# QTR.net
KiCad netlist of a schematic drawn in Altium Designer
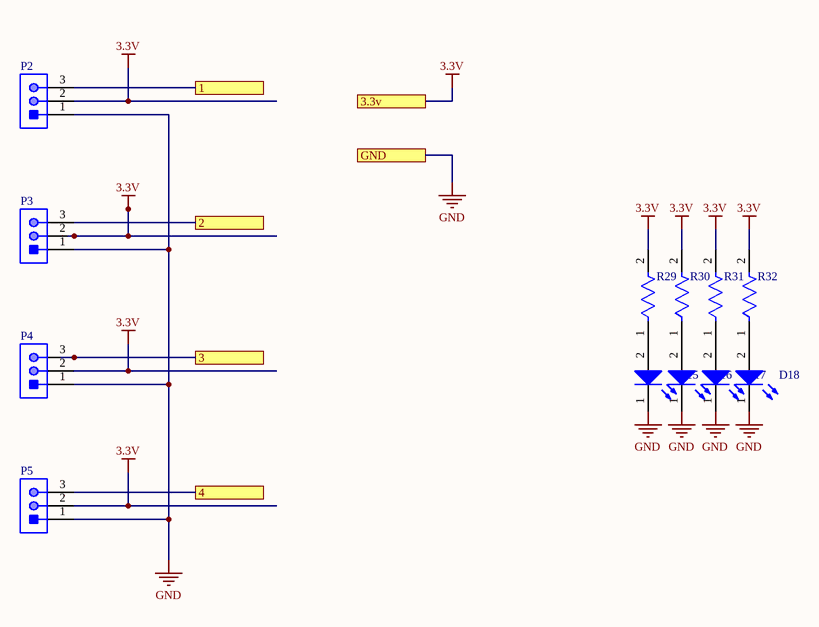
[diagram p0: QTR.SchDoc]

(export (version "E")
  (design (tool "Eeschema 10.0.6"))
  (components
    (comp (ref "D15")
      (value "150080BS75000")
      (footprint "WL-SMCW_0805_150080xx75000")
      (libsource (lib "Altium Content Vault") (part "LED_Blue_2A-1K"))
    )
    (comp (ref "D16")
      (value "150080BS75000")
      (footprint "WL-SMCW_0805_150080xx75000")
      (libsource (lib "Altium Content Vault") (part "LED_Blue_2A-1K"))
    )
    (comp (ref "D17")
      (value "150080BS75000")
      (footprint "WL-SMCW_0805_150080xx75000")
      (libsource (lib "Altium Content Vault") (part "LED_Blue_2A-1K"))
    )
    (comp (ref "D18")
      (value "150080BS75000")
      (footprint "WL-SMCW_0805_150080xx75000")
      (libsource (lib "Altium Content Vault") (part "LED_Blue_2A-1K"))
    )
    (comp (ref "P2")
      (value "B3B-PH-K-S(LF)(SN)")
      (footprint "JST-B3B-PH-K-S-3_V")
      (fields (field (name "MANUFACTURER") "JST"))
      (libsource (lib "Altium Content Vault") (part "CN-1P-M-R3"))
    )
    (comp (ref "P3")
      (value "B3B-PH-K-S(LF)(SN)")
      (footprint "JST-B3B-PH-K-S-3_V")
      (fields (field (name "MANUFACTURER") "JST"))
      (libsource (lib "Altium Content Vault") (part "CN-1P-M-R3"))
    )
    (comp (ref "P4")
      (value "B3B-PH-K-S(LF)(SN)")
      (footprint "JST-B3B-PH-K-S-3_V")
      (fields (field (name "MANUFACTURER") "JST"))
      (libsource (lib "Altium Content Vault") (part "CN-1P-M-R3"))
    )
    (comp (ref "P5")
      (value "B3B-PH-K-S(LF)(SN)")
      (footprint "JST-B3B-PH-K-S-3_V")
      (fields (field (name "MANUFACTURER") "JST"))
      (libsource (lib "Altium Content Vault") (part "CN-1P-M-R3"))
    )
    (comp (ref "R29")
      (value "ERJ-6ENF1500V")
      (footprint "FP-ERJ6EN-IPC_A")
      (fields (field (name "TOLERANCE") "1%"))
      (libsource (lib "Altium Content Vault") (part "1029c3af85768c4190bb7ad29bc67b5"))
    )
    (comp (ref "R30")
      (value "ERJ-6ENF1500V")
      (footprint "FP-ERJ6EN-IPC_A")
      (fields (field (name "TOLERANCE") "1%"))
      (libsource (lib "Altium Content Vault") (part "1029c3af85768c4190bb7ad29bc67b5"))
    )
    (comp (ref "R31")
      (value "ERJ-6ENF1500V")
      (footprint "FP-ERJ6EN-IPC_A")
      (fields (field (name "TOLERANCE") "1%"))
      (libsource (lib "Altium Content Vault") (part "1029c3af85768c4190bb7ad29bc67b5"))
    )
    (comp (ref "R32")
      (value "ERJ-6ENF1500V")
      (footprint "FP-ERJ6EN-IPC_A")
      (fields (field (name "TOLERANCE") "1%"))
      (libsource (lib "Altium Content Vault") (part "1029c3af85768c4190bb7ad29bc67b5"))
    )
  )
  (nets
    (net (code "1") (name "/1") (class "Default")
      (node (ref "P2") (pin "3") (pinfunction "3_3") (pintype "passive"))
    )
    (net (code "2") (name "/2") (class "Default")
      (node (ref "P3") (pin "3") (pinfunction "3_3") (pintype "passive"))
    )
    (net (code "3") (name "/3") (class "Default")
      (node (ref "P4") (pin "3") (pinfunction "3_3") (pintype "passive"))
    )
    (net (code "4") (name "/4") (class "Default")
      (node (ref "P5") (pin "3") (pinfunction "3_3") (pintype "passive"))
    )
    (net (code "5") (name "3.3V") (class "Default")
      (node (ref "P2") (pin "2") (pinfunction "2_2") (pintype "passive"))
      (node (ref "P3") (pin "2") (pinfunction "2_2") (pintype "passive"))
      (node (ref "P4") (pin "2") (pinfunction "2_2") (pintype "passive"))
      (node (ref "P5") (pin "2") (pinfunction "2_2") (pintype "passive"))
      (node (ref "R29") (pin "2") (pinfunction "2_2") (pintype "passive"))
      (node (ref "R30") (pin "2") (pinfunction "2_2") (pintype "passive"))
      (node (ref "R31") (pin "2") (pinfunction "2_2") (pintype "passive"))
      (node (ref "R32") (pin "2") (pinfunction "2_2") (pintype "passive"))
    )
    (net (code "6") (name "GND") (class "Default")
      (node (ref "D15") (pin "1") (pinfunction "K_1") (pintype "passive"))
      (node (ref "D16") (pin "1") (pinfunction "K_1") (pintype "passive"))
      (node (ref "D17") (pin "1") (pinfunction "K_1") (pintype "passive"))
      (node (ref "D18") (pin "1") (pinfunction "K_1") (pintype "passive"))
      (node (ref "P2") (pin "1") (pinfunction "1_1") (pintype "passive"))
      (node (ref "P3") (pin "1") (pinfunction "1_1") (pintype "passive"))
      (node (ref "P4") (pin "1") (pinfunction "1_1") (pintype "passive"))
      (node (ref "P5") (pin "1") (pinfunction "1_1") (pintype "passive"))
    )
    (net (code "7") (name "Net-(D15-A)") (class "Default")
      (node (ref "D15") (pin "2") (pinfunction "A_2") (pintype "passive"))
      (node (ref "R29") (pin "1") (pinfunction "1_1") (pintype "passive"))
    )
    (net (code "8") (name "Net-(D16-A)") (class "Default")
      (node (ref "D16") (pin "2") (pinfunction "A_2") (pintype "passive"))
      (node (ref "R30") (pin "1") (pinfunction "1_1") (pintype "passive"))
    )
    (net (code "9") (name "Net-(D17-A)") (class "Default")
      (node (ref "D17") (pin "2") (pinfunction "A_2") (pintype "passive"))
      (node (ref "R31") (pin "1") (pinfunction "1_1") (pintype "passive"))
    )
    (net (code "10") (name "Net-(D18-A)") (class "Default")
      (node (ref "D18") (pin "2") (pinfunction "A_2") (pintype "passive"))
      (node (ref "R32") (pin "1") (pinfunction "1_1") (pintype "passive"))
    )
  )
)
